# Sheet1.net
KiCad netlist of a schematic drawn in Altium Designer
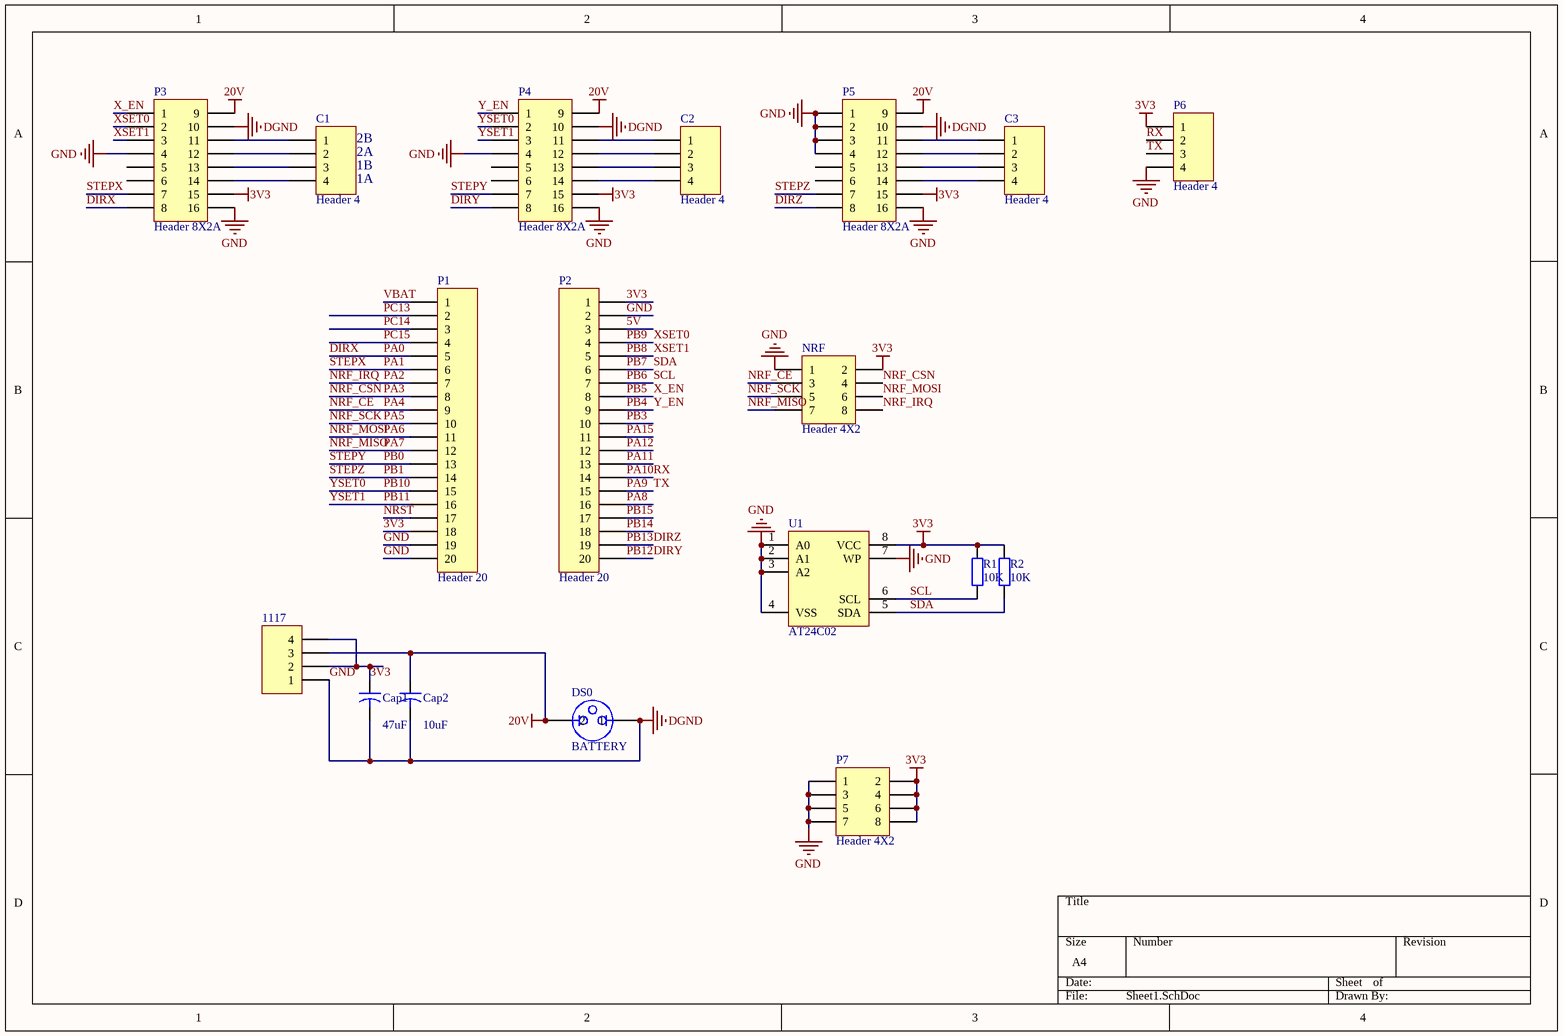
[diagram p0: Sheet1.SchDoc]

(export (version "E")
  (design (tool "Eeschema 10.0.6"))
  (components
    (comp (ref "1117")
      (value "Header 4")
      (footprint "SOT-223")
      (description "Header, 4-Pin")
      (fields (field (name "PUBLISHER") "Altium Limited"))
      (libsource (lib "") (part "Header 4_1"))
    )
    (comp (ref "C1")
      (value "Header 4")
      (footprint "HDR1X4")
      (description "Header, 4-Pin")
      (fields (field (name "PUBLISHER") "Altium Limited"))
      (libsource (lib "Miscellaneous Connectors") (part "Header 4"))
    )
    (comp (ref "C2")
      (value "Header 4")
      (footprint "HDR1X4")
      (description "Header, 4-Pin")
      (fields (field (name "PUBLISHER") "Altium Limited"))
      (libsource (lib "Miscellaneous Connectors") (part "Header 4"))
    )
    (comp (ref "C3")
      (value "Header 4")
      (footprint "HDR1X4")
      (description "Header, 4-Pin")
      (fields (field (name "PUBLISHER") "Altium Limited"))
      (libsource (lib "Miscellaneous Connectors") (part "Header 4"))
    )
    (comp (ref "Cap1")
      (value "47uF")
      (footprint "CAPR5-4X5")
      (description "Capacitor")
      (fields (field (name "Comment") "Cap2") (field (name "PUBLISHER") "Altium Limited"))
      (libsource (lib "Miscellaneous Devices") (part "Cap2"))
    )
    (comp (ref "Cap2")
      (value "10uF")
      (footprint "CAPR5-4X5")
      (description "Capacitor")
      (fields (field (name "Comment") "Cap2") (field (name "PUBLISHER") "Altium Limited"))
      (libsource (lib "Miscellaneous Devices") (part "Cap2"))
    )
    (comp (ref "DS0") (value "BATTERY") (footprint "9V") (libsource (lib "nucleo原理图库") (part "BATTERY")))
    (comp (ref "NRF")
      (value "Header 4X2")
      (footprint "HDR2X4")
      (description "Header, 4-Pin, Dual row")
      (fields (field (name "PUBLISHER") "Altium Limited"))
      (libsource (lib "Miscellaneous Connectors") (part "Header 4X2"))
    )
    (comp (ref "P1")
      (value "Header 20")
      (footprint "HDR1X20")
      (description "Header, 20-Pin")
      (fields (field (name "PUBLISHER") "Altium Limited"))
      (libsource (lib "") (part "Header 20_1"))
    )
    (comp (ref "P2")
      (value "Header 20")
      (footprint "HDR1X20")
      (description "Header, 20-Pin")
      (fields (field (name "PUBLISHER") "Altium Limited"))
      (libsource (lib "Miscellaneous Connectors") (part "Header 20"))
    )
    (comp (ref "P3")
      (value "Header 8X2A")
      (footprint "PCBComponent_1")
      (description "Header, 8-Pin, Dual row")
      (fields (field (name "PUBLISHER") "Altium Limited"))
      (libsource (lib "Miscellaneous Connectors") (part "Header 8X2A"))
    )
    (comp (ref "P4")
      (value "Header 8X2A")
      (footprint "PCBComponent_1")
      (description "Header, 8-Pin, Dual row")
      (fields (field (name "PUBLISHER") "Altium Limited"))
      (libsource (lib "Miscellaneous Connectors") (part "Header 8X2A"))
    )
    (comp (ref "P5")
      (value "Header 8X2A")
      (footprint "PCBComponent_1")
      (description "Header, 8-Pin, Dual row")
      (fields (field (name "PUBLISHER") "Altium Limited"))
      (libsource (lib "Miscellaneous Connectors") (part "Header 8X2A"))
    )
    (comp (ref "P6")
      (value "Header 4")
      (footprint "HDR1X4")
      (description "Header, 4-Pin")
      (fields (field (name "PUBLISHER") "Altium Limited"))
      (libsource (lib "Miscellaneous Connectors") (part "Header 4"))
    )
    (comp (ref "P7")
      (value "Header 4X2")
      (footprint "HDR2X4")
      (description "Header, 4-Pin, Dual row")
      (fields (field (name "PUBLISHER") "Altium Limited"))
      (libsource (lib "Miscellaneous Connectors") (part "Header 4X2"))
    )
    (comp (ref "R1")
      (value "10K")
      (footprint "R1/4")
      (description "Resistor")
      (fields (field (name "Comment") "Res2") (field (name "PUBLISHER") "Altium Limited"))
      (libsource (lib "nucleo原理图库") (part "Res2"))
    )
    (comp (ref "R2")
      (value "10K")
      (footprint "R1/4")
      (description "Resistor")
      (fields (field (name "Comment") "Res2") (field (name "PUBLISHER") "Altium Limited"))
      (libsource (lib "nucleo原理图库") (part "Res2"))
    )
    (comp (ref "U1")
      (value "AT24C02")
      (footprint "SOIC8P")
      (description "EEROM存储器")
      (libsource (lib "nucleo原理图库") (part "AT24C02"))
    )
  )
  (nets
    (net (code "1") (name "/5V") (class "Default")
      (node (ref "P2") (pin "3") (pinfunction "3_3") (pintype "passive"))
    )
    (net (code "2") (name "/DIRX") (class "Default")
      (node (ref "P1") (pin "5") (pinfunction "5_5") (pintype "passive"))
      (node (ref "P3") (pin "8") (pinfunction "8_8") (pintype "passive"))
    )
    (net (code "3") (name "/DIRY") (class "Default")
      (node (ref "P2") (pin "20") (pinfunction "20_20") (pintype "passive"))
      (node (ref "P4") (pin "8") (pinfunction "8_8") (pintype "passive"))
    )
    (net (code "4") (name "/DIRZ") (class "Default")
      (node (ref "P2") (pin "19") (pinfunction "19_19") (pintype "passive"))
      (node (ref "P5") (pin "8") (pinfunction "8_8") (pintype "passive"))
    )
    (net (code "5") (name "/NRF_CE") (class "Default")
      (node (ref "NRF") (pin "3") (pinfunction "3_3") (pintype "passive"))
      (node (ref "P1") (pin "9") (pinfunction "9_9") (pintype "passive"))
    )
    (net (code "6") (name "/NRF_CSN") (class "Default")
      (node (ref "NRF") (pin "4") (pinfunction "4_4") (pintype "passive"))
      (node (ref "P1") (pin "8") (pinfunction "8_8") (pintype "passive"))
    )
    (net (code "7") (name "/NRF_IRQ") (class "Default")
      (node (ref "NRF") (pin "8") (pinfunction "8_8") (pintype "passive"))
      (node (ref "P1") (pin "7") (pinfunction "7_7") (pintype "passive"))
    )
    (net (code "8") (name "/NRF_MISO") (class "Default")
      (node (ref "NRF") (pin "7") (pinfunction "7_7") (pintype "passive"))
      (node (ref "P1") (pin "12") (pinfunction "12_12") (pintype "passive"))
    )
    (net (code "9") (name "/NRF_MOSI") (class "Default")
      (node (ref "NRF") (pin "6") (pinfunction "6_6") (pintype "passive"))
      (node (ref "P1") (pin "11") (pinfunction "11_11") (pintype "passive"))
    )
    (net (code "10") (name "/NRF_SCK") (class "Default")
      (node (ref "NRF") (pin "5") (pinfunction "5_5") (pintype "passive"))
      (node (ref "P1") (pin "10") (pinfunction "10_10") (pintype "passive"))
    )
    (net (code "11") (name "/NRST") (class "Default")
      (node (ref "P1") (pin "17") (pinfunction "17_17") (pintype "passive"))
    )
    (net (code "12") (name "/PA1") (class "Default")
      (node (ref "P1") (pin "6") (pinfunction "6_6") (pintype "passive"))
      (node (ref "P3") (pin "7") (pinfunction "7_7") (pintype "passive"))
    )
    (net (code "13") (name "/PA8") (class "Default")
      (node (ref "P2") (pin "16") (pinfunction "16_16") (pintype "passive"))
    )
    (net (code "14") (name "/PA9") (class "Default")
      (node (ref "P2") (pin "15") (pinfunction "15_15") (pintype "passive"))
      (node (ref "P6") (pin "3") (pinfunction "3_3") (pintype "passive"))
    )
    (net (code "15") (name "/PA10") (class "Default")
      (node (ref "P2") (pin "14") (pinfunction "14_14") (pintype "passive"))
      (node (ref "P6") (pin "2") (pinfunction "2_2") (pintype "passive"))
    )
    (net (code "16") (name "/PA11") (class "Default")
      (node (ref "P2") (pin "13") (pinfunction "13_13") (pintype "passive"))
    )
    (net (code "17") (name "/PA12") (class "Default")
      (node (ref "P2") (pin "12") (pinfunction "12_12") (pintype "passive"))
    )
    (net (code "18") (name "/PA15") (class "Default")
      (node (ref "P2") (pin "11") (pinfunction "11_11") (pintype "passive"))
    )
    (net (code "19") (name "/PB0") (class "Default")
      (node (ref "P1") (pin "13") (pinfunction "13_13") (pintype "passive"))
      (node (ref "P4") (pin "7") (pinfunction "7_7") (pintype "passive"))
    )
    (net (code "20") (name "/PB1") (class "Default")
      (node (ref "P1") (pin "14") (pinfunction "14_14") (pintype "passive"))
      (node (ref "P5") (pin "7") (pinfunction "7_7") (pintype "passive"))
    )
    (net (code "21") (name "/PB3") (class "Default")
      (node (ref "P2") (pin "10") (pinfunction "10_10") (pintype "passive"))
    )
    (net (code "22") (name "/PB4") (class "Default")
      (node (ref "P2") (pin "9") (pinfunction "9_9") (pintype "passive"))
      (node (ref "P4") (pin "1") (pinfunction "1_1") (pintype "passive"))
    )
    (net (code "23") (name "/PB5") (class "Default")
      (node (ref "P2") (pin "8") (pinfunction "8_8") (pintype "passive"))
      (node (ref "P3") (pin "1") (pinfunction "1_1") (pintype "passive"))
    )
    (net (code "24") (name "/PB6") (class "Default")
      (node (ref "P2") (pin "7") (pinfunction "7_7") (pintype "passive"))
      (node (ref "R1") (pin "1") (pinfunction "1_1") (pintype "passive"))
      (node (ref "U1") (pin "6") (pinfunction "SCL_6") (pintype "passive"))
    )
    (net (code "25") (name "/PB7") (class "Default")
      (node (ref "P2") (pin "6") (pinfunction "6_6") (pintype "passive"))
      (node (ref "R2") (pin "1") (pinfunction "1_1") (pintype "passive"))
      (node (ref "U1") (pin "5") (pinfunction "SDA_5") (pintype "passive"))
    )
    (net (code "26") (name "/PB8") (class "Default")
      (node (ref "P2") (pin "5") (pinfunction "5_5") (pintype "passive"))
      (node (ref "P3") (pin "3") (pinfunction "3_3") (pintype "passive"))
    )
    (net (code "27") (name "/PB9") (class "Default")
      (node (ref "P2") (pin "4") (pinfunction "4_4") (pintype "passive"))
      (node (ref "P3") (pin "2") (pinfunction "2_2") (pintype "passive"))
    )
    (net (code "28") (name "/PB10") (class "Default")
      (node (ref "P1") (pin "15") (pinfunction "15_15") (pintype "passive"))
      (node (ref "P4") (pin "2") (pinfunction "2_2") (pintype "passive"))
    )
    (net (code "29") (name "/PB11") (class "Default")
      (node (ref "P1") (pin "16") (pinfunction "16_16") (pintype "passive"))
      (node (ref "P4") (pin "3") (pinfunction "3_3") (pintype "passive"))
    )
    (net (code "30") (name "/PB14") (class "Default")
      (node (ref "P2") (pin "18") (pinfunction "18_18") (pintype "passive"))
    )
    (net (code "31") (name "/PB15") (class "Default")
      (node (ref "P2") (pin "17") (pinfunction "17_17") (pintype "passive"))
    )
    (net (code "32") (name "/PC13") (class "Default")
      (node (ref "P1") (pin "2") (pinfunction "2_2") (pintype "passive"))
    )
    (net (code "33") (name "/PC14") (class "Default")
      (node (ref "P1") (pin "3") (pinfunction "3_3") (pintype "passive"))
    )
    (net (code "34") (name "/PC15") (class "Default")
      (node (ref "P1") (pin "4") (pinfunction "4_4") (pintype "passive"))
    )
    (net (code "35") (name "/VBAT") (class "Default")
      (node (ref "P1") (pin "1") (pinfunction "1_1") (pintype "passive"))
    )
    (net (code "36") (name "3V3") (class "Default")
      (node (ref "1117") (pin "2") (pinfunction "2_2") (pintype "passive"))
      (node (ref "1117") (pin "4") (pinfunction "4_4") (pintype "passive"))
      (node (ref "Cap1") (pin "1") (pinfunction "1_1") (pintype "passive"))
      (node (ref "NRF") (pin "2") (pinfunction "2_2") (pintype "passive"))
      (node (ref "P1") (pin "18") (pinfunction "18_18") (pintype "passive"))
      (node (ref "P2") (pin "1") (pinfunction "1_1") (pintype "passive"))
      (node (ref "P3") (pin "15") (pinfunction "15_15") (pintype "passive"))
      (node (ref "P4") (pin "15") (pinfunction "15_15") (pintype "passive"))
      (node (ref "P5") (pin "15") (pinfunction "15_15") (pintype "passive"))
      (node (ref "P6") (pin "1") (pinfunction "1_1") (pintype "passive"))
      (node (ref "P7") (pin "2") (pinfunction "2_2") (pintype "passive"))
      (node (ref "P7") (pin "4") (pinfunction "4_4") (pintype "passive"))
      (node (ref "P7") (pin "6") (pinfunction "6_6") (pintype "passive"))
      (node (ref "P7") (pin "8") (pinfunction "8_8") (pintype "passive"))
      (node (ref "R1") (pin "2") (pinfunction "2_2") (pintype "passive"))
      (node (ref "R2") (pin "2") (pinfunction "2_2") (pintype "passive"))
      (node (ref "U1") (pin "8") (pinfunction "VCC_8") (pintype "passive"))
    )
    (net (code "37") (name "20V") (class "Default")
      (node (ref "1117") (pin "3") (pinfunction "3_3") (pintype "passive"))
      (node (ref "Cap2") (pin "1") (pinfunction "1_1") (pintype "passive"))
      (node (ref "DS0") (pin "2") (pinfunction "2_2") (pintype "passive"))
      (node (ref "P3") (pin "9") (pinfunction "9_9") (pintype "passive"))
      (node (ref "P4") (pin "9") (pinfunction "9_9") (pintype "passive"))
      (node (ref "P5") (pin "9") (pinfunction "9_9") (pintype "passive"))
    )
    (net (code "38") (name "DGND") (class "Default")
      (node (ref "1117") (pin "1") (pinfunction "1_1") (pintype "passive"))
      (node (ref "Cap1") (pin "2") (pinfunction "2_2") (pintype "passive"))
      (node (ref "Cap2") (pin "2") (pinfunction "2_2") (pintype "passive"))
      (node (ref "DS0") (pin "1") (pinfunction "1_1") (pintype "passive"))
      (node (ref "NRF") (pin "1") (pinfunction "1_1") (pintype "passive"))
      (node (ref "P1") (pin "19") (pinfunction "19_19") (pintype "passive"))
      (node (ref "P1") (pin "20") (pinfunction "20_20") (pintype "passive"))
      (node (ref "P2") (pin "2") (pinfunction "2_2") (pintype "passive"))
      (node (ref "P3") (pin "10") (pinfunction "10_10") (pintype "passive"))
      (node (ref "P3") (pin "16") (pinfunction "16_16") (pintype "passive"))
      (node (ref "P3") (pin "4") (pinfunction "4_4") (pintype "passive"))
      (node (ref "P4") (pin "10") (pinfunction "10_10") (pintype "passive"))
      (node (ref "P4") (pin "16") (pinfunction "16_16") (pintype "passive"))
      (node (ref "P4") (pin "4") (pinfunction "4_4") (pintype "passive"))
      (node (ref "P5") (pin "1") (pinfunction "1_1") (pintype "passive"))
      (node (ref "P5") (pin "10") (pinfunction "10_10") (pintype "passive"))
      (node (ref "P5") (pin "16") (pinfunction "16_16") (pintype "passive"))
      (node (ref "P5") (pin "2") (pinfunction "2_2") (pintype "passive"))
      (node (ref "P5") (pin "3") (pinfunction "3_3") (pintype "passive"))
      (node (ref "P5") (pin "4") (pinfunction "4_4") (pintype "passive"))
      (node (ref "P6") (pin "4") (pinfunction "4_4") (pintype "passive"))
      (node (ref "P7") (pin "1") (pinfunction "1_1") (pintype "passive"))
      (node (ref "P7") (pin "3") (pinfunction "3_3") (pintype "passive"))
      (node (ref "P7") (pin "5") (pinfunction "5_5") (pintype "passive"))
      (node (ref "P7") (pin "7") (pinfunction "7_7") (pintype "passive"))
      (node (ref "U1") (pin "1") (pinfunction "A0_1") (pintype "passive"))
      (node (ref "U1") (pin "2") (pinfunction "A1_2") (pintype "passive"))
      (node (ref "U1") (pin "3") (pinfunction "A2_3") (pintype "passive"))
      (node (ref "U1") (pin "4") (pinfunction "VSS_4") (pintype "passive"))
      (node (ref "U1") (pin "7") (pinfunction "WP_7") (pintype "passive"))
    )
    (net (code "39") (name "Net-(C1-Pad1)") (class "Default")
      (node (ref "C1") (pin "1") (pinfunction "1_1") (pintype "passive"))
      (node (ref "P3") (pin "11") (pinfunction "11_11") (pintype "passive"))
    )
    (net (code "40") (name "Net-(C1-Pad2)") (class "Default")
      (node (ref "C1") (pin "2") (pinfunction "2_2") (pintype "passive"))
      (node (ref "P3") (pin "12") (pinfunction "12_12") (pintype "passive"))
    )
    (net (code "41") (name "Net-(C1-Pad3)") (class "Default")
      (node (ref "C1") (pin "3") (pinfunction "3_3") (pintype "passive"))
      (node (ref "P3") (pin "13") (pinfunction "13_13") (pintype "passive"))
    )
    (net (code "42") (name "Net-(C1-Pad4)") (class "Default")
      (node (ref "C1") (pin "4") (pinfunction "4_4") (pintype "passive"))
      (node (ref "P3") (pin "14") (pinfunction "14_14") (pintype "passive"))
    )
    (net (code "43") (name "Net-(C2-Pad1)") (class "Default")
      (node (ref "C2") (pin "1") (pinfunction "1_1") (pintype "passive"))
      (node (ref "P4") (pin "11") (pinfunction "11_11") (pintype "passive"))
    )
    (net (code "44") (name "Net-(C2-Pad2)") (class "Default")
      (node (ref "C2") (pin "2") (pinfunction "2_2") (pintype "passive"))
      (node (ref "P4") (pin "12") (pinfunction "12_12") (pintype "passive"))
    )
    (net (code "45") (name "Net-(C2-Pad3)") (class "Default")
      (node (ref "C2") (pin "3") (pinfunction "3_3") (pintype "passive"))
      (node (ref "P4") (pin "13") (pinfunction "13_13") (pintype "passive"))
    )
    (net (code "46") (name "Net-(C2-Pad4)") (class "Default")
      (node (ref "C2") (pin "4") (pinfunction "4_4") (pintype "passive"))
      (node (ref "P4") (pin "14") (pinfunction "14_14") (pintype "passive"))
    )
    (net (code "47") (name "Net-(C3-Pad1)") (class "Default")
      (node (ref "C3") (pin "1") (pinfunction "1_1") (pintype "passive"))
      (node (ref "P5") (pin "11") (pinfunction "11_11") (pintype "passive"))
    )
    (net (code "48") (name "Net-(C3-Pad2)") (class "Default")
      (node (ref "C3") (pin "2") (pinfunction "2_2") (pintype "passive"))
      (node (ref "P5") (pin "12") (pinfunction "12_12") (pintype "passive"))
    )
    (net (code "49") (name "Net-(C3-Pad3)") (class "Default")
      (node (ref "C3") (pin "3") (pinfunction "3_3") (pintype "passive"))
      (node (ref "P5") (pin "13") (pinfunction "13_13") (pintype "passive"))
    )
    (net (code "50") (name "Net-(C3-Pad4)") (class "Default")
      (node (ref "C3") (pin "4") (pinfunction "4_4") (pintype "passive"))
      (node (ref "P5") (pin "14") (pinfunction "14_14") (pintype "passive"))
    )
    (net (code "51") (name "unconnected-(P3-Pad5)") (class "Default")
      (node (ref "P3") (pin "5") (pinfunction "5_5") (pintype "passive"))
    )
    (net (code "52") (name "unconnected-(P3-Pad6)") (class "Default")
      (node (ref "P3") (pin "6") (pinfunction "6_6") (pintype "passive"))
    )
    (net (code "53") (name "unconnected-(P4-Pad5)") (class "Default")
      (node (ref "P4") (pin "5") (pinfunction "5_5") (pintype "passive"))
    )
    (net (code "54") (name "unconnected-(P4-Pad6)") (class "Default")
      (node (ref "P4") (pin "6") (pinfunction "6_6") (pintype "passive"))
    )
    (net (code "55") (name "unconnected-(P5-Pad5)") (class "Default")
      (node (ref "P5") (pin "5") (pinfunction "5_5") (pintype "passive"))
    )
    (net (code "56") (name "unconnected-(P5-Pad6)") (class "Default")
      (node (ref "P5") (pin "6") (pinfunction "6_6") (pintype "passive"))
    )
  )
)
